# A9G_Minimal_Hardware.net
KiCad netlist of a schematic drawn in EAGLE
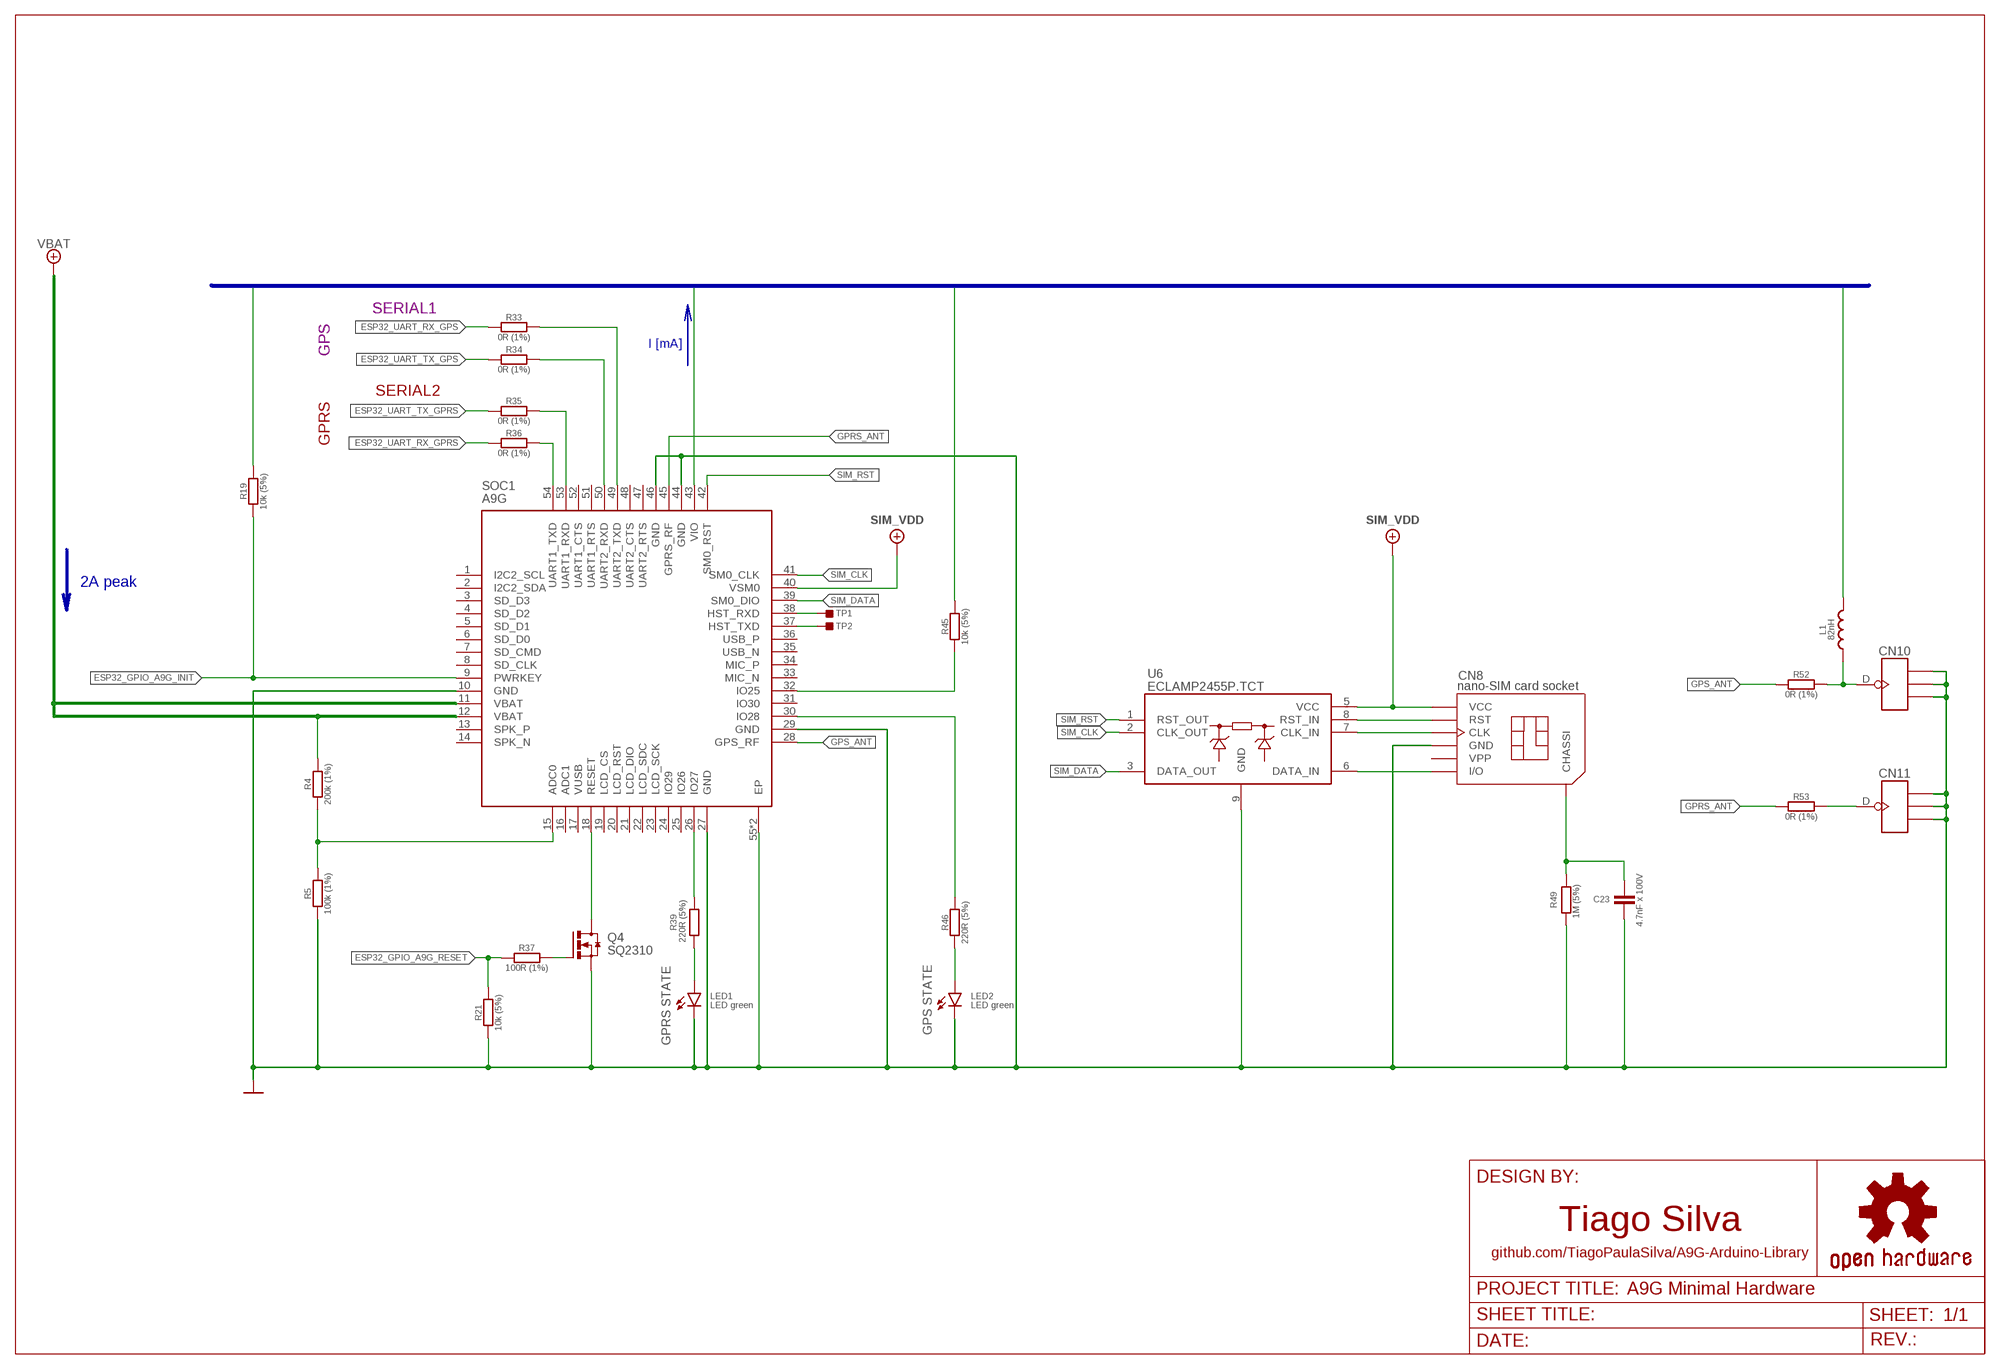
[diagram p0: schematic, sheet 1]

(export (version "E")
  (design (tool "Eeschema 10.0.6"))
  (components
    (comp (ref "C23")
      (value "4.7nF x 100V")
      (footprint "eagle-import:C0402")
      (fields (field (name "PARTNO") "GRM155R72A472KA01D"))
      (libsource (lib "eagle-import") (part "C_0402"))
    )
    (comp (ref "CN8")
      (value "nano-SIM card socket")
      (footprint "eagle-import:SIM-CARD")
      (fields (field (name "PARTNO") "693043020611"))
      (libsource (lib "eagle-import") (part "SIM-CARD"))
    )
    (comp (ref "CN10")
      (value "ANTENNA-U-FL")
      (footprint "eagle-import:4P-U-FL")
      (fields (field (name "PARTNO") "U.FL-R-SMT-1(10)"))
      (libsource (lib "eagle-import") (part "ANTENNA-U-FL"))
    )
    (comp (ref "CN11")
      (value "ANTENNA-U-FL")
      (footprint "eagle-import:4P-U-FL")
      (fields (field (name "PARTNO") "U.FL-R-SMT-1(10)"))
      (libsource (lib "eagle-import") (part "ANTENNA-U-FL"))
    )
    (comp (ref "L1")
      (value "82nH")
      (footprint "eagle-import:L0402")
      (fields (field (name "PARTNO") "LQG15WH82NG02D"))
      (libsource (lib "eagle-import") (part "L_0402"))
    )
    (comp (ref "LED1")
      (value "LED green")
      (footprint "eagle-import:LED-0603")
      (fields (field (name "PARTNO") "LTST-C191KGKT") (field (name "PN") "150060VS75000"))
      (libsource (lib "eagle-import") (part "LED-0603"))
    )
    (comp (ref "LED2")
      (value "LED green")
      (footprint "eagle-import:LED-0603")
      (fields (field (name "PARTNO") "LTST-C191KGKT") (field (name "PN") "150060VS75000"))
      (libsource (lib "eagle-import") (part "LED-0603"))
    )
    (comp (ref "Q4")
      (value "N-Channel MOSFET")
      (footprint "eagle-import:SOT23-3")
      (fields (field (name "FAMILY") "SQ2310") (field (name "PARTNO") "SQ2310ES-T1_GE3"))
      (libsource (lib "eagle-import") (part "N-FET-ENHANCEMENT-SQ2310"))
    )
    (comp (ref "R4")
      (value "200k (1%)")
      (footprint "eagle-import:R0402")
      (libsource (lib "eagle-import") (part "R_0402"))
    )
    (comp (ref "R5")
      (value "100k (1%)")
      (footprint "eagle-import:R0402")
      (libsource (lib "eagle-import") (part "R_0402"))
    )
    (comp (ref "R19")
      (value "10k (5%)")
      (footprint "eagle-import:R0402")
      (fields (field (name "PARTNO") "RC0402FR-0710KL"))
      (libsource (lib "eagle-import") (part "R_0402"))
    )
    (comp (ref "R21")
      (value "10k (5%)")
      (footprint "eagle-import:R0402")
      (libsource (lib "eagle-import") (part "R_0402"))
    )
    (comp (ref "R33")
      (value "0R (1%)")
      (footprint "eagle-import:R0402")
      (libsource (lib "eagle-import") (part "My-RLC_35509816_R_0402"))
    )
    (comp (ref "R34")
      (value "0R (1%)")
      (footprint "eagle-import:R0402")
      (libsource (lib "eagle-import") (part "My-RLC_35509816_R_0402"))
    )
    (comp (ref "R35")
      (value "0R (1%)")
      (footprint "eagle-import:R0402")
      (libsource (lib "eagle-import") (part "My-RLC_35509816_R_0402"))
    )
    (comp (ref "R36")
      (value "0R (1%)")
      (footprint "eagle-import:R0402")
      (libsource (lib "eagle-import") (part "My-RLC_35509816_R_0402"))
    )
    (comp (ref "R37")
      (value "100R (1%)")
      (footprint "eagle-import:R0402")
      (fields (field (name "PARTNO") "RC0402FR-07100RL"))
      (libsource (lib "eagle-import") (part "R_0402"))
    )
    (comp (ref "R39")
      (value "220R (5%)")
      (footprint "eagle-import:R0402")
      (libsource (lib "eagle-import") (part "R_0402"))
    )
    (comp (ref "R45")
      (value "10k (5%)")
      (footprint "eagle-import:R0402")
      (fields (field (name "PARTNO") "RC0402FR-0710KL"))
      (libsource (lib "eagle-import") (part "R_0402"))
    )
    (comp (ref "R46")
      (value "220R (5%)")
      (footprint "eagle-import:R0402")
      (libsource (lib "eagle-import") (part "R_0402"))
    )
    (comp (ref "R49")
      (value "1M (5%)")
      (footprint "eagle-import:R0402")
      (fields (field (name "PARTNO") "RC0402JR-071ML"))
      (libsource (lib "eagle-import") (part "R_0402"))
    )
    (comp (ref "R52")
      (value "0R (1%)")
      (footprint "eagle-import:R0402")
      (fields (field (name "PARTNO") "RC0402FR-070RL"))
      (libsource (lib "eagle-import") (part "R_0402"))
    )
    (comp (ref "R53")
      (value "0R (1%)")
      (footprint "eagle-import:R0402")
      (fields (field (name "PARTNO") "RC0402FR-070RL"))
      (libsource (lib "eagle-import") (part "R_0402"))
    )
    (comp (ref "SOC1")
      (value "A9G")
      (footprint "eagle-import:A9G")
      (libsource (lib "eagle-import") (part "A9G"))
    )
    (comp (ref "TP1")
      (value "ATP2-30")
      (footprint "eagle-import:ATP-30")
      (libsource (lib "eagle-import") (part "ATP2-30"))
    )
    (comp (ref "TP2")
      (value "ATP2-30")
      (footprint "eagle-import:ATP-30")
      (libsource (lib "eagle-import") (part "ATP2-30"))
    )
    (comp (ref "U6")
      (value "ECLAMP2455P.TCT")
      (footprint "eagle-import:SLP2116P8")
      (fields (field (name "MOUSER_PART_NUMBER") "947-ECLAMP2455P.TCT"))
      (libsource (lib "eagle-import") (part "ECLAMP2455P.TCT"))
    )
  )
  (nets
    (net (code "1") (name "/VIO") (class "Default")
      (node (ref "L1") (pin "1") (pinfunction "1_1") (pintype "passive"))
      (node (ref "R19") (pin "2") (pinfunction "2_2") (pintype "passive"))
      (node (ref "R45") (pin "2") (pinfunction "2_2") (pintype "passive"))
      (node (ref "SOC1") (pin "43") (pinfunction "VIO_43") (pintype "bidirectional"))
    )
    (net (code "2") (name "0V") (class "Default")
      (node (ref "C23") (pin "1") (pinfunction "1_1") (pintype "passive"))
      (node (ref "CN10") (pin "GND1") (pinfunction "GND1_GND1") (pintype "bidirectional"))
      (node (ref "CN10") (pin "GND2") (pinfunction "GND2_GND2") (pintype "bidirectional"))
      (node (ref "CN10") (pin "GND3") (pinfunction "GND3_GND3") (pintype "bidirectional"))
      (node (ref "CN11") (pin "GND1") (pinfunction "GND1_GND1") (pintype "bidirectional"))
      (node (ref "CN11") (pin "GND2") (pinfunction "GND2_GND2") (pintype "bidirectional"))
      (node (ref "CN11") (pin "GND3") (pinfunction "GND3_GND3") (pintype "bidirectional"))
      (node (ref "CN8") (pin "C5") (pinfunction "GND_C5") (pintype "power_in"))
      (node (ref "LED1") (pin "C") (pinfunction "K_C") (pintype "passive"))
      (node (ref "LED2") (pin "C") (pinfunction "K_C") (pintype "passive"))
      (node (ref "Q4") (pin "2") (pinfunction "S_2") (pintype "passive"))
      (node (ref "R21") (pin "1") (pinfunction "1_1") (pintype "passive"))
      (node (ref "R49") (pin "2") (pinfunction "2_2") (pintype "passive"))
      (node (ref "R5") (pin "1") (pinfunction "1_1") (pintype "passive"))
      (node (ref "SOC1") (pin "10") (pinfunction "GND_10") (pintype "bidirectional"))
      (node (ref "SOC1") (pin "27") (pinfunction "GND_27") (pintype "bidirectional"))
      (node (ref "SOC1") (pin "29") (pinfunction "GND_29") (pintype "bidirectional"))
      (node (ref "SOC1") (pin "44") (pinfunction "GND_44") (pintype "bidirectional"))
      (node (ref "SOC1") (pin "46") (pinfunction "GND_46") (pintype "bidirectional"))
      (node (ref "SOC1") (pin "55") (pinfunction "EP_55") (pintype "bidirectional"))
      (node (ref "SOC1") (pin "56") (pinfunction "EP_56") (pintype "bidirectional"))
      (node (ref "U6") (pin "9") (pinfunction "GND_9") (pintype "bidirectional"))
    )
    (net (code "3") (name "ESP32_GPIO_A9G_INIT") (class "Default")
      (node (ref "R19") (pin "1") (pinfunction "1_1") (pintype "passive"))
      (node (ref "SOC1") (pin "9") (pinfunction "PWRKEY_9") (pintype "bidirectional"))
    )
    (net (code "4") (name "ESP32_GPIO_A9G_RESET") (class "Default")
      (node (ref "R21") (pin "2") (pinfunction "2_2") (pintype "passive"))
      (node (ref "R37") (pin "1") (pinfunction "1_1") (pintype "passive"))
    )
    (net (code "5") (name "ESP32_UART_RX_GPRS") (class "Default")
      (node (ref "R36") (pin "1") (pinfunction "1_1") (pintype "passive"))
    )
    (net (code "6") (name "ESP32_UART_RX_GPS") (class "Default")
      (node (ref "R33") (pin "1") (pinfunction "1_1") (pintype "passive"))
    )
    (net (code "7") (name "ESP32_UART_TX_GPRS") (class "Default")
      (node (ref "R35") (pin "1") (pinfunction "1_1") (pintype "passive"))
    )
    (net (code "8") (name "ESP32_UART_TX_GPS") (class "Default")
      (node (ref "R34") (pin "1") (pinfunction "1_1") (pintype "passive"))
    )
    (net (code "9") (name "GPRS_ANT") (class "Default")
      (node (ref "R53") (pin "1") (pinfunction "1_1") (pintype "passive"))
      (node (ref "SOC1") (pin "45") (pinfunction "GPRS_RF_45") (pintype "bidirectional"))
    )
    (net (code "10") (name "GPS_ANT") (class "Default")
      (node (ref "R52") (pin "1") (pinfunction "1_1") (pintype "passive"))
      (node (ref "SOC1") (pin "28") (pinfunction "GPS_RF_28") (pintype "bidirectional"))
    )
    (net (code "11") (name "Net-(C23-Pad2)") (class "Default")
      (node (ref "C23") (pin "2") (pinfunction "2_2") (pintype "passive"))
      (node (ref "CN8") (pin "P1") (pinfunction "CHASSI_P1") (pintype "bidirectional"))
      (node (ref "CN8") (pin "P2") (pinfunction "CHASSI_P2") (pintype "bidirectional"))
      (node (ref "CN8") (pin "P3") (pinfunction "CHASSI_P3") (pintype "bidirectional"))
      (node (ref "CN8") (pin "P4") (pinfunction "CHASSI_P4") (pintype "bidirectional"))
      (node (ref "CN8") (pin "P5") (pinfunction "CHASSI_P5") (pintype "bidirectional"))
      (node (ref "CN8") (pin "P6") (pinfunction "CHASSI_P6") (pintype "bidirectional"))
      (node (ref "R49") (pin "1") (pinfunction "1_1") (pintype "passive"))
    )
    (net (code "12") (name "Net-(CN8-CLK)") (class "Default")
      (node (ref "CN8") (pin "C3") (pinfunction "CLK_C3") (pintype "input"))
      (node (ref "U6") (pin "7") (pinfunction "CLK_IN_7") (pintype "bidirectional"))
    )
    (net (code "13") (name "Net-(CN8-I{slash}O)") (class "Default")
      (node (ref "CN8") (pin "C7") (pinfunction "I/O_C7") (pintype "bidirectional"))
      (node (ref "U6") (pin "6") (pinfunction "DATA_IN_6") (pintype "bidirectional"))
    )
    (net (code "14") (name "Net-(CN8-RST)") (class "Default")
      (node (ref "CN8") (pin "C2") (pinfunction "RST_C2") (pintype "input"))
      (node (ref "U6") (pin "8") (pinfunction "RST_IN_8") (pintype "bidirectional"))
    )
    (net (code "15") (name "Net-(CN10-PadD)") (class "Default")
      (node (ref "CN10") (pin "D") (pinfunction "D_D") (pintype "bidirectional"))
      (node (ref "L1") (pin "2") (pinfunction "2_2") (pintype "passive"))
      (node (ref "R52") (pin "2") (pinfunction "2_2") (pintype "passive"))
    )
    (net (code "16") (name "Net-(CN11-PadD)") (class "Default")
      (node (ref "CN11") (pin "D") (pinfunction "D_D") (pintype "bidirectional"))
      (node (ref "R53") (pin "2") (pinfunction "2_2") (pintype "passive"))
    )
    (net (code "17") (name "Net-(LED1-PadA)") (class "Default")
      (node (ref "LED1") (pin "A") (pinfunction "A_A") (pintype "passive"))
      (node (ref "R39") (pin "1") (pinfunction "1_1") (pintype "passive"))
    )
    (net (code "18") (name "Net-(LED2-PadA)") (class "Default")
      (node (ref "LED2") (pin "A") (pinfunction "A_A") (pintype "passive"))
      (node (ref "R46") (pin "1") (pinfunction "1_1") (pintype "passive"))
    )
    (net (code "19") (name "Net-(Q4-D)") (class "Default")
      (node (ref "Q4") (pin "3") (pinfunction "D_3") (pintype "passive"))
      (node (ref "SOC1") (pin "18") (pinfunction "RESET_18") (pintype "bidirectional"))
    )
    (net (code "20") (name "Net-(Q4-G)") (class "Default")
      (node (ref "Q4") (pin "1") (pinfunction "G_1") (pintype "passive"))
      (node (ref "R37") (pin "2") (pinfunction "2_2") (pintype "passive"))
    )
    (net (code "21") (name "Net-(SOC1-ADC0)") (class "Default")
      (node (ref "R4") (pin "1") (pinfunction "1_1") (pintype "passive"))
      (node (ref "R5") (pin "2") (pinfunction "2_2") (pintype "passive"))
      (node (ref "SOC1") (pin "15") (pinfunction "ADC0_15") (pintype "bidirectional"))
    )
    (net (code "22") (name "Net-(SOC1-HST_RXD)") (class "Default")
      (node (ref "SOC1") (pin "38") (pinfunction "HST_RXD_38") (pintype "bidirectional"))
      (node (ref "TP1") (pin "P") (pinfunction "P_P") (pintype "passive"))
    )
    (net (code "23") (name "Net-(SOC1-HST_TXD)") (class "Default")
      (node (ref "SOC1") (pin "37") (pinfunction "HST_TXD_37") (pintype "bidirectional"))
      (node (ref "TP2") (pin "P") (pinfunction "P_P") (pintype "passive"))
    )
    (net (code "24") (name "Net-(SOC1-IO25)") (class "Default")
      (node (ref "R45") (pin "1") (pinfunction "1_1") (pintype "passive"))
      (node (ref "SOC1") (pin "32") (pinfunction "IO25_32") (pintype "bidirectional"))
    )
    (net (code "25") (name "Net-(SOC1-IO27)") (class "Default")
      (node (ref "R39") (pin "2") (pinfunction "2_2") (pintype "passive"))
      (node (ref "SOC1") (pin "26") (pinfunction "IO27_26") (pintype "bidirectional"))
    )
    (net (code "26") (name "Net-(SOC1-IO28)") (class "Default")
      (node (ref "R46") (pin "2") (pinfunction "2_2") (pintype "passive"))
      (node (ref "SOC1") (pin "30") (pinfunction "IO28_30") (pintype "bidirectional"))
    )
    (net (code "27") (name "Net-(SOC1-UART1_RXD)") (class "Default")
      (node (ref "R35") (pin "2") (pinfunction "2_2") (pintype "passive"))
      (node (ref "SOC1") (pin "53") (pinfunction "UART1_RXD_53") (pintype "bidirectional"))
    )
    (net (code "28") (name "Net-(SOC1-UART1_TXD)") (class "Default")
      (node (ref "R36") (pin "2") (pinfunction "2_2") (pintype "passive"))
      (node (ref "SOC1") (pin "54") (pinfunction "UART1_TXD_54") (pintype "bidirectional"))
    )
    (net (code "29") (name "Net-(SOC1-UART2_RXD)") (class "Default")
      (node (ref "R34") (pin "2") (pinfunction "2_2") (pintype "passive"))
      (node (ref "SOC1") (pin "50") (pinfunction "UART2_RXD_50") (pintype "bidirectional"))
    )
    (net (code "30") (name "Net-(SOC1-UART2_TXD)") (class "Default")
      (node (ref "R33") (pin "2") (pinfunction "2_2") (pintype "passive"))
      (node (ref "SOC1") (pin "49") (pinfunction "UART2_TXD_49") (pintype "bidirectional"))
    )
    (net (code "31") (name "SIM_CLK") (class "Default")
      (node (ref "SOC1") (pin "41") (pinfunction "SM0_CLK_41") (pintype "bidirectional"))
      (node (ref "U6") (pin "2") (pinfunction "CLK_OUT_2") (pintype "bidirectional"))
    )
    (net (code "32") (name "SIM_DATA") (class "Default")
      (node (ref "SOC1") (pin "39") (pinfunction "SM0_DIO_39") (pintype "bidirectional"))
      (node (ref "U6") (pin "3") (pinfunction "DATA_OUT_3") (pintype "bidirectional"))
    )
    (net (code "33") (name "SIM_RST") (class "Default")
      (node (ref "SOC1") (pin "42") (pinfunction "SM0_RST_42") (pintype "bidirectional"))
      (node (ref "U6") (pin "1") (pinfunction "RST_OUT_1") (pintype "bidirectional"))
    )
    (net (code "34") (name "SIM_VDD") (class "Default")
      (node (ref "CN8") (pin "C1") (pinfunction "VCC_C1") (pintype "power_in"))
      (node (ref "SOC1") (pin "40") (pinfunction "VSM0_40") (pintype "bidirectional"))
      (node (ref "U6") (pin "5") (pinfunction "VCC_5") (pintype "bidirectional"))
    )
    (net (code "35") (name "VBAT") (class "Default")
      (node (ref "R4") (pin "2") (pinfunction "2_2") (pintype "passive"))
      (node (ref "SOC1") (pin "11") (pinfunction "VBAT_11") (pintype "bidirectional"))
      (node (ref "SOC1") (pin "12") (pinfunction "VBAT_12") (pintype "bidirectional"))
    )
    (net (code "36") (name "unconnected-(CN8-VPP-PadC6)") (class "Default")
      (node (ref "CN8") (pin "C6") (pinfunction "VPP_C6") (pintype "bidirectional"))
    )
    (net (code "37") (name "unconnected-(SOC1-ADC1-Pad16)") (class "Default")
      (node (ref "SOC1") (pin "16") (pinfunction "ADC1_16") (pintype "bidirectional"))
    )
    (net (code "38") (name "unconnected-(SOC1-I2C2_SCL-Pad1)") (class "Default")
      (node (ref "SOC1") (pin "1") (pinfunction "I2C2_SCL_1") (pintype "bidirectional"))
    )
    (net (code "39") (name "unconnected-(SOC1-I2C2_SDA-Pad2)") (class "Default")
      (node (ref "SOC1") (pin "2") (pinfunction "I2C2_SDA_2") (pintype "bidirectional"))
    )
    (net (code "40") (name "unconnected-(SOC1-IO26-Pad25)") (class "Default")
      (node (ref "SOC1") (pin "25") (pinfunction "IO26_25") (pintype "bidirectional"))
    )
    (net (code "41") (name "unconnected-(SOC1-IO29-Pad24)") (class "Default")
      (node (ref "SOC1") (pin "24") (pinfunction "IO29_24") (pintype "bidirectional"))
    )
    (net (code "42") (name "unconnected-(SOC1-IO30-Pad31)") (class "Default")
      (node (ref "SOC1") (pin "31") (pinfunction "IO30_31") (pintype "bidirectional"))
    )
    (net (code "43") (name "unconnected-(SOC1-LCD_CS-Pad19)") (class "Default")
      (node (ref "SOC1") (pin "19") (pinfunction "LCD_CS_19") (pintype "bidirectional"))
    )
    (net (code "44") (name "unconnected-(SOC1-LCD_DIO-Pad21)") (class "Default")
      (node (ref "SOC1") (pin "21") (pinfunction "LCD_DIO_21") (pintype "bidirectional"))
    )
    (net (code "45") (name "unconnected-(SOC1-LCD_RST-Pad20)") (class "Default")
      (node (ref "SOC1") (pin "20") (pinfunction "LCD_RST_20") (pintype "bidirectional"))
    )
    (net (code "46") (name "unconnected-(SOC1-LCD_SCK-Pad23)") (class "Default")
      (node (ref "SOC1") (pin "23") (pinfunction "LCD_SCK_23") (pintype "bidirectional"))
    )
    (net (code "47") (name "unconnected-(SOC1-LCD_SDC-Pad22)") (class "Default")
      (node (ref "SOC1") (pin "22") (pinfunction "LCD_SDC_22") (pintype "bidirectional"))
    )
    (net (code "48") (name "unconnected-(SOC1-MIC_N-Pad33)") (class "Default")
      (node (ref "SOC1") (pin "33") (pinfunction "MIC_N_33") (pintype "bidirectional"))
    )
    (net (code "49") (name "unconnected-(SOC1-MIC_P-Pad34)") (class "Default")
      (node (ref "SOC1") (pin "34") (pinfunction "MIC_P_34") (pintype "bidirectional"))
    )
    (net (code "50") (name "unconnected-(SOC1-SD_CLK-Pad8)") (class "Default")
      (node (ref "SOC1") (pin "8") (pinfunction "SD_CLK_8") (pintype "bidirectional"))
    )
    (net (code "51") (name "unconnected-(SOC1-SD_CMD-Pad7)") (class "Default")
      (node (ref "SOC1") (pin "7") (pinfunction "SD_CMD_7") (pintype "bidirectional"))
    )
    (net (code "52") (name "unconnected-(SOC1-SD_D0-Pad6)") (class "Default")
      (node (ref "SOC1") (pin "6") (pinfunction "SD_D0_6") (pintype "bidirectional"))
    )
    (net (code "53") (name "unconnected-(SOC1-SD_D1-Pad5)") (class "Default")
      (node (ref "SOC1") (pin "5") (pinfunction "SD_D1_5") (pintype "bidirectional"))
    )
    (net (code "54") (name "unconnected-(SOC1-SD_D2-Pad4)") (class "Default")
      (node (ref "SOC1") (pin "4") (pinfunction "SD_D2_4") (pintype "bidirectional"))
    )
    (net (code "55") (name "unconnected-(SOC1-SD_D3-Pad3)") (class "Default")
      (node (ref "SOC1") (pin "3") (pinfunction "SD_D3_3") (pintype "bidirectional"))
    )
    (net (code "56") (name "unconnected-(SOC1-SPK_N-Pad14)") (class "Default")
      (node (ref "SOC1") (pin "14") (pinfunction "SPK_N_14") (pintype "bidirectional"))
    )
    (net (code "57") (name "unconnected-(SOC1-SPK_P-Pad13)") (class "Default")
      (node (ref "SOC1") (pin "13") (pinfunction "SPK_P_13") (pintype "bidirectional"))
    )
    (net (code "58") (name "unconnected-(SOC1-UART1_CTS-Pad52)") (class "Default")
      (node (ref "SOC1") (pin "52") (pinfunction "UART1_CTS_52") (pintype "bidirectional"))
    )
    (net (code "59") (name "unconnected-(SOC1-UART1_RTS-Pad51)") (class "Default")
      (node (ref "SOC1") (pin "51") (pinfunction "UART1_RTS_51") (pintype "bidirectional"))
    )
    (net (code "60") (name "unconnected-(SOC1-UART2_CTS-Pad48)") (class "Default")
      (node (ref "SOC1") (pin "48") (pinfunction "UART2_CTS_48") (pintype "bidirectional"))
    )
    (net (code "61") (name "unconnected-(SOC1-UART2_RTS-Pad47)") (class "Default")
      (node (ref "SOC1") (pin "47") (pinfunction "UART2_RTS_47") (pintype "bidirectional"))
    )
    (net (code "62") (name "unconnected-(SOC1-USB_N-Pad35)") (class "Default")
      (node (ref "SOC1") (pin "35") (pinfunction "USB_N_35") (pintype "bidirectional"))
    )
    (net (code "63") (name "unconnected-(SOC1-USB_P-Pad36)") (class "Default")
      (node (ref "SOC1") (pin "36") (pinfunction "USB_P_36") (pintype "bidirectional"))
    )
    (net (code "64") (name "unconnected-(SOC1-VUSB-Pad17)") (class "Default")
      (node (ref "SOC1") (pin "17") (pinfunction "VUSB_17") (pintype "bidirectional"))
    )
  )
)
